# Pi_Zero_PITS.net
KiCad netlist of a schematic drawn in EAGLE
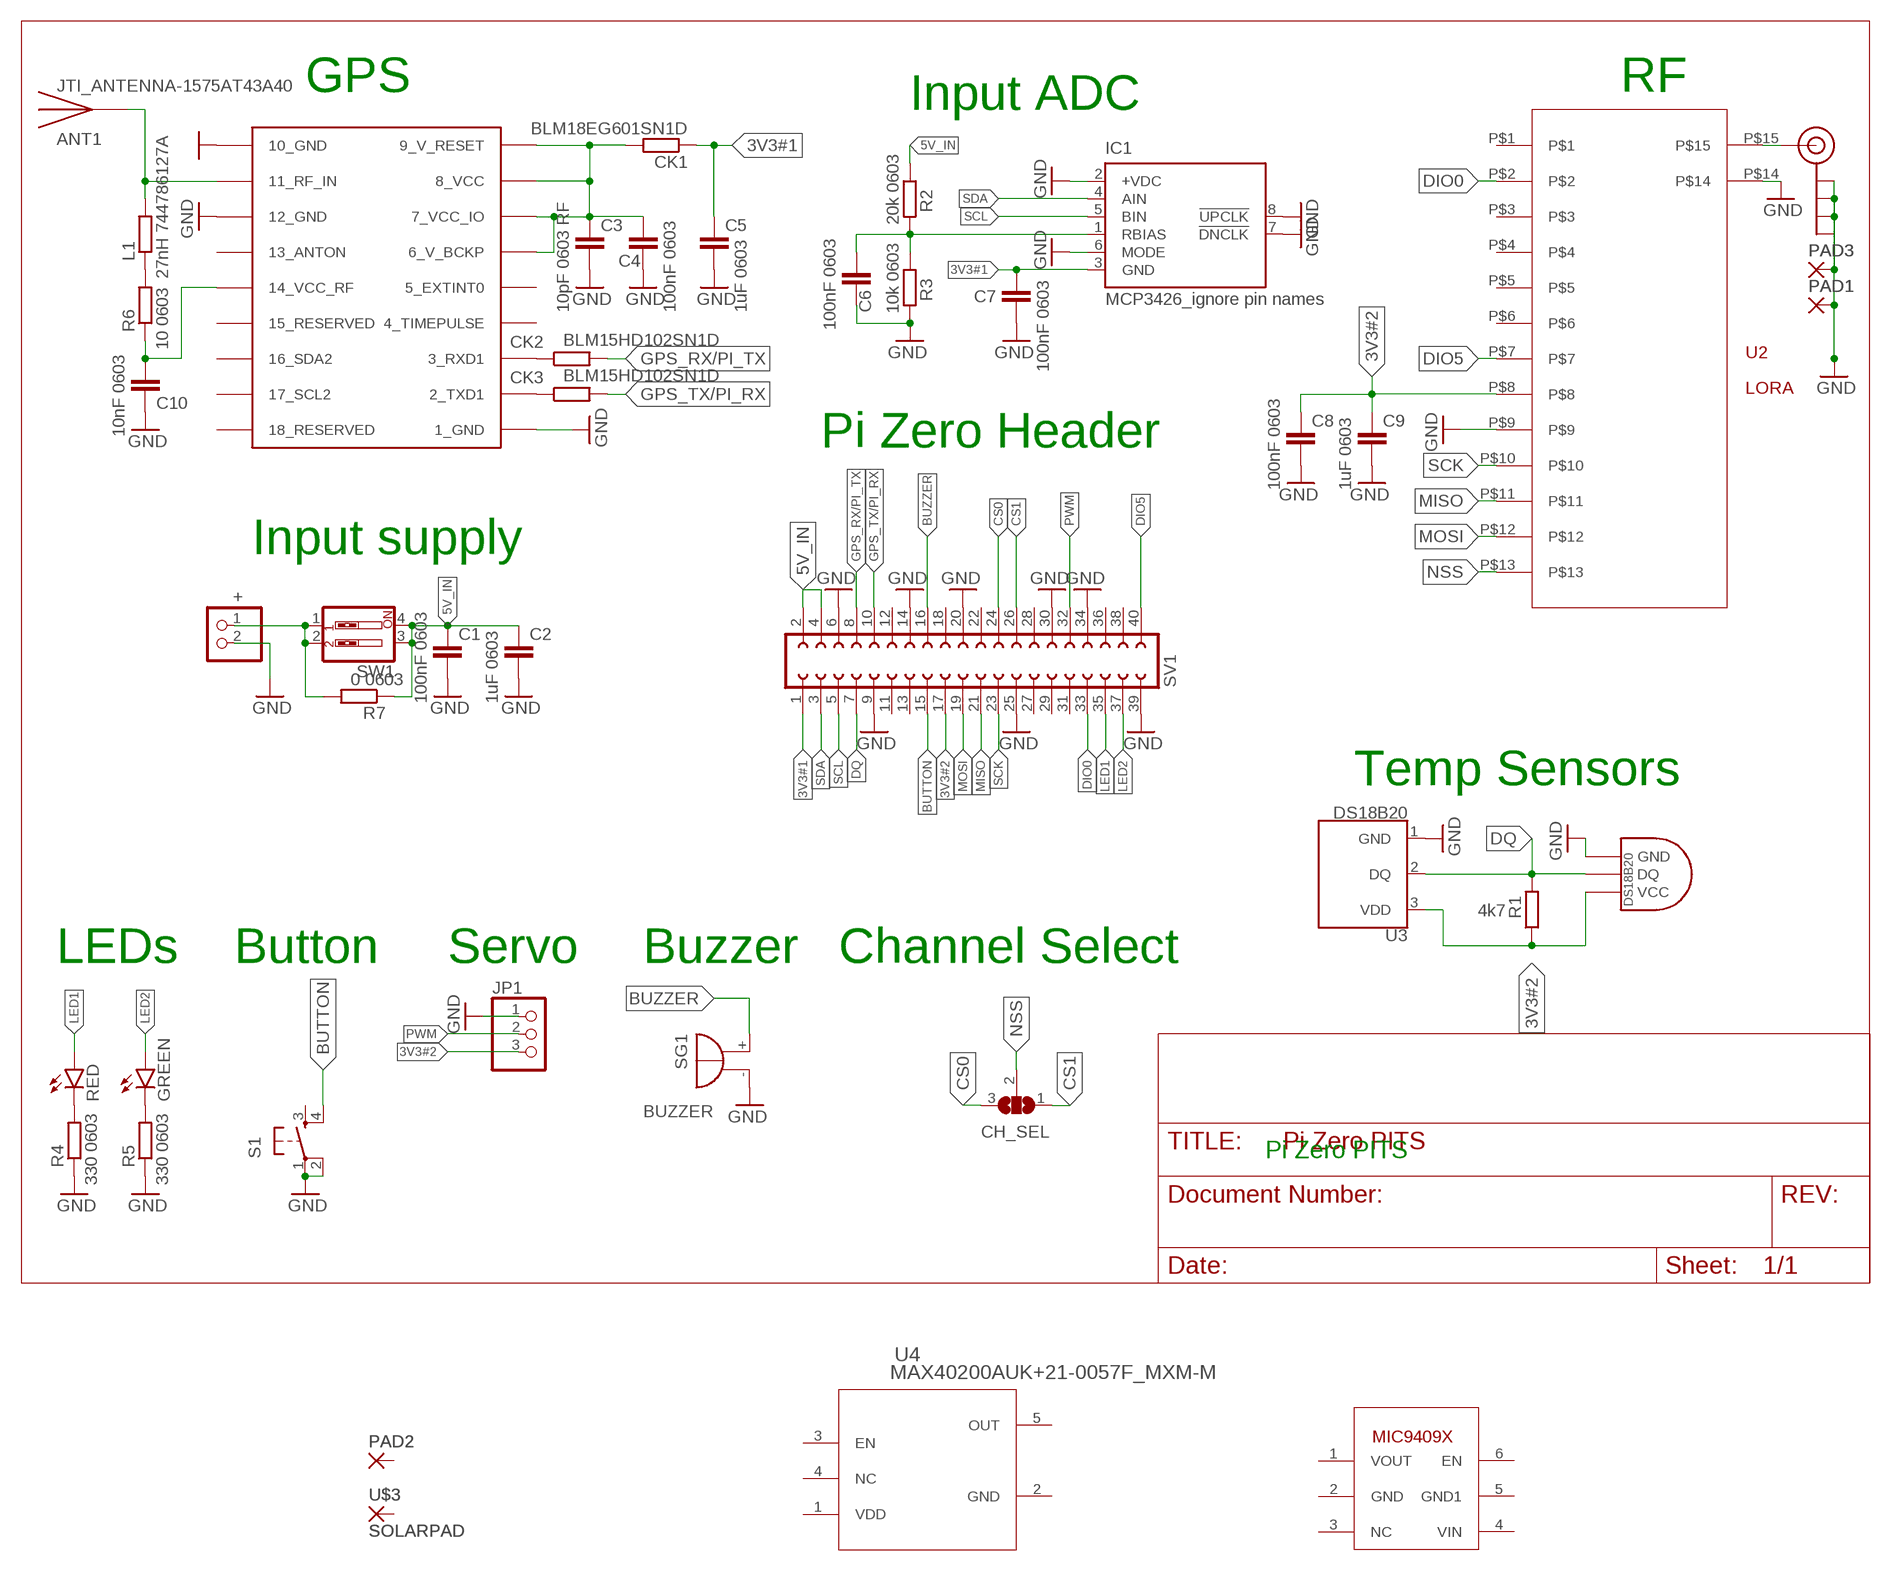
[diagram p0: schematic, sheet 1]

(export (version "E")
  (design (tool "Eeschema 10.0.6"))
  (components
    (comp (ref "+")
      (value "PINHD-1X2")
      (footprint "eagle-import:1X02")
      (libsource (lib "eagle-import") (part "PINHD-1X2"))
    )
    (comp (ref "ANT1")
      (value "JTI_ANTENNA-1575AT43A40")
      (footprint "eagle-import:JTI_ANTENNA-1575AT43A40")
      (libsource (lib "eagle-import") (part "JTI_ANTENNA-1575AT43A40"))
    )
    (comp (ref "C1")
      (value "100nF 0603")
      (footprint "eagle-import:C0603K")
      (libsource (lib "eagle-import") (part "C-EUC0603K"))
    )
    (comp (ref "C2")
      (value "1uF 0603")
      (footprint "eagle-import:C0603K")
      (libsource (lib "eagle-import") (part "C-EUC0603K"))
    )
    (comp (ref "C3")
      (value "10pF 0603 RF")
      (footprint "eagle-import:C0603K")
      (libsource (lib "eagle-import") (part "C-EUC0603K"))
    )
    (comp (ref "C4")
      (value "100nF 0603")
      (footprint "eagle-import:C0603K")
      (libsource (lib "eagle-import") (part "C-EUC0603K"))
    )
    (comp (ref "C5")
      (value "1uF 0603")
      (footprint "eagle-import:C0603K")
      (libsource (lib "eagle-import") (part "C-EUC0603K"))
    )
    (comp (ref "C6")
      (value "100nF 0603")
      (footprint "eagle-import:C0603K")
      (libsource (lib "eagle-import") (part "C-EUC0603K"))
    )
    (comp (ref "C7")
      (value "100nF 0603")
      (footprint "eagle-import:C0603K")
      (libsource (lib "eagle-import") (part "C-EUC0603K"))
    )
    (comp (ref "C8")
      (value "100nF 0603")
      (footprint "eagle-import:C0603K")
      (libsource (lib "eagle-import") (part "C-EUC0603K"))
    )
    (comp (ref "C9")
      (value "1uF 0603")
      (footprint "eagle-import:C0603K")
      (libsource (lib "eagle-import") (part "C-EUC0603K"))
    )
    (comp (ref "C10")
      (value "10nF 0603")
      (footprint "eagle-import:C0603K")
      (libsource (lib "eagle-import") (part "C-EUC0603K"))
    )
    (comp (ref "CH_SEL")
      (value "SJ2W")
      (footprint "eagle-import:SJ_2")
      (libsource (lib "eagle-import") (part "SJ2W"))
    )
    (comp (ref "CK1")
      (value "BLM18EG601SN1D")
      (footprint "eagle-import:R0603")
      (libsource (lib "eagle-import") (part "R-EU_R0603"))
    )
    (comp (ref "CK2")
      (value "BLM15HD102SN1D")
      (footprint "eagle-import:R0402")
      (libsource (lib "eagle-import") (part "R-EU_R0402"))
    )
    (comp (ref "CK3")
      (value "BLM15HD102SN1D")
      (footprint "eagle-import:R0402")
      (libsource (lib "eagle-import") (part "R-EU_R0402"))
    )
    (comp (ref "GREEN")
      (value "LEDSML0603")
      (footprint "eagle-import:SML0603")
      (libsource (lib "eagle-import") (part "LEDSML0603"))
    )
    (comp (ref "IC1")
      (value "MCP3426_ignore pin names")
      (footprint "eagle-import:SOIC08")
      (libsource (lib "eagle-import") (part "LS7183-SOIC"))
    )
    (comp (ref "J$2")
      (value "SMA_EDGE")
      (footprint "eagle-import:SMA-EDGE")
      (libsource (lib "eagle-import") (part "SMA_EDGE"))
    )
    (comp (ref "JP1")
      (value "PINHD-1X3")
      (footprint "eagle-import:1X03")
      (libsource (lib "eagle-import") (part "PINHD-1X3"))
    )
    (comp (ref "L1")
      (value "27nH 744786127A")
      (footprint "eagle-import:R0603")
      (libsource (lib "eagle-import") (part "R-EU_R0603"))
    )
    (comp (ref "PAD1")
      (value "SMD5")
      (footprint "eagle-import:SMD2,54-5,08")
      (libsource (lib "eagle-import") (part "SMD5"))
    )
    (comp (ref "PAD2")
      (value "SMD2SMD_KW")
      (footprint "eagle-import:SMD_SMALL")
      (libsource (lib "eagle-import") (part "SMD2SMD_KW"))
    )
    (comp (ref "PAD3")
      (value "SMD5")
      (footprint "eagle-import:SMD2,54-5,08")
      (libsource (lib "eagle-import") (part "SMD5"))
    )
    (comp (ref "R1")
      (value "4k7")
      (footprint "eagle-import:R0603")
      (libsource (lib "eagle-import") (part "R-EU_R0603"))
    )
    (comp (ref "R2")
      (value "20k 0603")
      (footprint "eagle-import:R0603")
      (libsource (lib "eagle-import") (part "R-EU_R0603"))
    )
    (comp (ref "R3")
      (value "10k 0603")
      (footprint "eagle-import:R0603")
      (libsource (lib "eagle-import") (part "R-EU_R0603"))
    )
    (comp (ref "R4")
      (value "330 0603")
      (footprint "eagle-import:R0603")
      (libsource (lib "eagle-import") (part "R-EU_R0603"))
    )
    (comp (ref "R5")
      (value "330 0603")
      (footprint "eagle-import:R0603")
      (libsource (lib "eagle-import") (part "R-EU_R0603"))
    )
    (comp (ref "R6")
      (value "10 0603")
      (footprint "eagle-import:R0603")
      (libsource (lib "eagle-import") (part "R-EU_R0603"))
    )
    (comp (ref "R7")
      (value "0 0603")
      (footprint "eagle-import:R0603")
      (libsource (lib "eagle-import") (part "R-EU_R0603"))
    )
    (comp (ref "RED")
      (value "LEDSML0603")
      (footprint "eagle-import:SML0603")
      (libsource (lib "eagle-import") (part "LEDSML0603"))
    )
    (comp (ref "S1")
      (value "DTS-6")
      (footprint "eagle-import:DTS-6")
      (libsource (lib "eagle-import") (part "DTS-6"))
    )
    (comp (ref "SG1")
      (value "BUZZER")
      (footprint "eagle-import:BMT1205XH7.5")
      (libsource (lib "eagle-import") (part "BMT1205XH7.5"))
    )
    (comp (ref "SV1")
      (value "FE20-2")
      (footprint "eagle-import:FE20-2")
      (libsource (lib "eagle-import") (part "FE20-2"))
    )
    (comp (ref "SW1")
      (value "SW_DIP-2")
      (footprint "eagle-import:EDG-02")
      (libsource (lib "eagle-import") (part "SW_DIP-2"))
    )
    (comp (ref "U$2")
      (value "MIC9409X_MIC9409X")
      (footprint "eagle-import:MIC9409X_DCK_R-PDSO-G6")
      (libsource (lib "eagle-import") (part "MIC9409X_MIC9409X"))
    )
    (comp (ref "U$3")
      (value "SOLARPAD")
      (footprint "eagle-import:SOLARMOUNT")
      (libsource (lib "eagle-import") (part "SOLARPAD"))
    )
    (comp (ref "U$4")
      (value "DS1820SOIC")
      (footprint "eagle-import:DS18B20_SOIC")
      (libsource (lib "eagle-import") (part "DS1820SOIC"))
    )
    (comp (ref "U1")
      (value "U1")
      (footprint "eagle-import:UBLOX_MAX-6")
      (libsource (lib "eagle-import") (part "UBLOX_MAX-6"))
    )
    (comp (ref "U2")
      (value "LORA")
      (footprint "eagle-import:LORA_DRF")
      (libsource (lib "eagle-import") (part "LORA"))
    )
    (comp (ref "U3")
      (value "DS18B20")
      (footprint "eagle-import:TO-92-AMMO")
      (libsource (lib "eagle-import") (part "DS18B20"))
    )
    (comp (ref "U4")
      (value "MAX40200AUK+21-0057F_MXM-M")
      (footprint "eagle-import:21-0057F_MXM-M")
      (fields
        (field (name "MANUFACTURER_PART_NUMBER") "MAX40200AUK+")
        (field (name "COPYRIGHT") "Copyright (C) 2018 Accelerated Designs. All rights reserved")
      )
      (libsource (lib "eagle-import") (part "MAX40200AUK+21-0057F_MXM-M"))
    )
  )
  (nets
    (net (code "1") (name "/VDD") (class "Default")
      (node (ref "U4") (pin "1") (pinfunction "VDD_1") (pintype "power_in"))
    )
    (net (code "2") (name "3V3#1") (class "Default")
      (node (ref "C5") (pin "1") (pinfunction "1_1") (pintype "passive"))
      (node (ref "C7") (pin "1") (pinfunction "1_1") (pintype "passive"))
      (node (ref "CK1") (pin "1") (pinfunction "1_1") (pintype "passive"))
      (node (ref "IC1") (pin "3") (pinfunction "GND_3") (pintype "power_in"))
      (node (ref "SV1") (pin "1") (pinfunction "1_1") (pintype "passive"))
    )
    (net (code "3") (name "3V3#2") (class "Default")
      (node (ref "C8") (pin "1") (pinfunction "1_1") (pintype "passive"))
      (node (ref "C9") (pin "1") (pinfunction "1_1") (pintype "passive"))
      (node (ref "JP1") (pin "3") (pinfunction "3_3") (pintype "passive"))
      (node (ref "R1") (pin "1") (pinfunction "1_1") (pintype "passive"))
      (node (ref "SV1") (pin "17") (pinfunction "17_17") (pintype "passive"))
      (node (ref "U$4") (pin "VCC") (pinfunction "VCC_VCC") (pintype "power_in"))
      (node (ref "U2") (pin "P$8") (pinfunction "P$8_P$8") (pintype "bidirectional"))
      (node (ref "U3") (pin "3") (pinfunction "VDD_3") (pintype "power_in"))
    )
    (net (code "4") (name "5V_IN") (class "Default")
      (node (ref "C1") (pin "1") (pinfunction "1_1") (pintype "passive"))
      (node (ref "C2") (pin "1") (pinfunction "1_1") (pintype "passive"))
      (node (ref "R2") (pin "1") (pinfunction "1_1") (pintype "passive"))
      (node (ref "R7") (pin "1") (pinfunction "1_1") (pintype "passive"))
      (node (ref "SV1") (pin "2") (pinfunction "2_2") (pintype "passive"))
      (node (ref "SV1") (pin "4") (pinfunction "4_4") (pintype "passive"))
      (node (ref "SW1") (pin "3") (pinfunction "3_3") (pintype "passive"))
      (node (ref "SW1") (pin "4") (pinfunction "4_4") (pintype "passive"))
    )
    (net (code "5") (name "BUTTON") (class "Default")
      (node (ref "S1") (pin "4") (pinfunction "4_4") (pintype "passive"))
      (node (ref "SV1") (pin "15") (pinfunction "15_15") (pintype "passive"))
    )
    (net (code "6") (name "BUZZER") (class "Default")
      (node (ref "SG1") (pin "+") (pinfunction "+_+") (pintype "passive"))
      (node (ref "SV1") (pin "16") (pinfunction "16_16") (pintype "passive"))
    )
    (net (code "7") (name "CS0") (class "Default")
      (node (ref "CH_SEL") (pin "3") (pinfunction "3_3") (pintype "passive"))
      (node (ref "SV1") (pin "24") (pinfunction "24_24") (pintype "passive"))
    )
    (net (code "8") (name "CS1") (class "Default")
      (node (ref "CH_SEL") (pin "1") (pinfunction "1_1") (pintype "passive"))
      (node (ref "SV1") (pin "26") (pinfunction "26_26") (pintype "passive"))
    )
    (net (code "9") (name "DIO0") (class "Default")
      (node (ref "SV1") (pin "33") (pinfunction "33_33") (pintype "passive"))
      (node (ref "U2") (pin "P$2") (pinfunction "P$2_P$2") (pintype "bidirectional"))
    )
    (net (code "10") (name "DIO5") (class "Default")
      (node (ref "SV1") (pin "40") (pinfunction "40_40") (pintype "passive"))
      (node (ref "U2") (pin "P$7") (pinfunction "P$7_P$7") (pintype "bidirectional"))
    )
    (net (code "11") (name "DQ") (class "Default")
      (node (ref "R1") (pin "2") (pinfunction "2_2") (pintype "passive"))
      (node (ref "SV1") (pin "7") (pinfunction "7_7") (pintype "passive"))
      (node (ref "U$4") (pin "DQ") (pinfunction "DQ_DQ") (pintype "bidirectional"))
      (node (ref "U3") (pin "2") (pinfunction "DQ_2") (pintype "bidirectional"))
    )
    (net (code "12") (name "GND") (class "Default")
      (node (ref "+") (pin "2") (pinfunction "2_2") (pintype "passive"))
      (node (ref "C1") (pin "2") (pinfunction "2_2") (pintype "passive"))
      (node (ref "C10") (pin "2") (pinfunction "2_2") (pintype "passive"))
      (node (ref "C2") (pin "2") (pinfunction "2_2") (pintype "passive"))
      (node (ref "C3") (pin "2") (pinfunction "2_2") (pintype "passive"))
      (node (ref "C4") (pin "2") (pinfunction "2_2") (pintype "passive"))
      (node (ref "C5") (pin "2") (pinfunction "2_2") (pintype "passive"))
      (node (ref "C6") (pin "2") (pinfunction "2_2") (pintype "passive"))
      (node (ref "C7") (pin "2") (pinfunction "2_2") (pintype "passive"))
      (node (ref "C8") (pin "2") (pinfunction "2_2") (pintype "passive"))
      (node (ref "C9") (pin "2") (pinfunction "2_2") (pintype "passive"))
      (node (ref "IC1") (pin "2") (pinfunction "+VDC_2") (pintype "input"))
      (node (ref "IC1") (pin "6") (pinfunction "MODE_6") (pintype "input"))
      (node (ref "IC1") (pin "7") (pinfunction "~{DNCLK}_7") (pintype "input"))
      (node (ref "IC1") (pin "8") (pinfunction "~{UPCLK}_8") (pintype "input"))
      (node (ref "J$2") (pin "GND@0") (pinfunction "GND_GND@0") (pintype "bidirectional"))
      (node (ref "J$2") (pin "GND@1") (pinfunction "GND_GND@1") (pintype "bidirectional"))
      (node (ref "J$2") (pin "GND@2") (pinfunction "GND_GND@2") (pintype "bidirectional"))
      (node (ref "J$2") (pin "GND@3") (pinfunction "GND_GND@3") (pintype "bidirectional"))
      (node (ref "JP1") (pin "1") (pinfunction "1_1") (pintype "passive"))
      (node (ref "PAD1") (pin "1") (pinfunction "P_1") (pintype "passive"))
      (node (ref "PAD3") (pin "1") (pinfunction "P_1") (pintype "passive"))
      (node (ref "R3") (pin "2") (pinfunction "2_2") (pintype "passive"))
      (node (ref "R4") (pin "1") (pinfunction "1_1") (pintype "passive"))
      (node (ref "R5") (pin "1") (pinfunction "1_1") (pintype "passive"))
      (node (ref "S1") (pin "1") (pinfunction "1_1") (pintype "passive"))
      (node (ref "S1") (pin "2") (pinfunction "2_2") (pintype "passive"))
      (node (ref "SG1") (pin "-") (pinfunction "-_-") (pintype "passive"))
      (node (ref "SV1") (pin "14") (pinfunction "14_14") (pintype "passive"))
      (node (ref "SV1") (pin "20") (pinfunction "20_20") (pintype "passive"))
      (node (ref "SV1") (pin "25") (pinfunction "25_25") (pintype "passive"))
      (node (ref "SV1") (pin "30") (pinfunction "30_30") (pintype "passive"))
      (node (ref "SV1") (pin "34") (pinfunction "34_34") (pintype "passive"))
      (node (ref "SV1") (pin "39") (pinfunction "39_39") (pintype "passive"))
      (node (ref "SV1") (pin "6") (pinfunction "6_6") (pintype "passive"))
      (node (ref "SV1") (pin "9") (pinfunction "9_9") (pintype "passive"))
      (node (ref "U$4") (pin "GND") (pinfunction "GND_GND") (pintype "power_in"))
      (node (ref "U1") (pin "10_GND") (pinfunction "10_GND_10_GND") (pintype "power_in"))
      (node (ref "U1") (pin "12_GND") (pinfunction "12_GND_12_GND") (pintype "power_in"))
      (node (ref "U1") (pin "1_GND") (pinfunction "1_GND_1_GND") (pintype "power_in"))
      (node (ref "U2") (pin "P$14") (pinfunction "P$14_P$14") (pintype "bidirectional"))
      (node (ref "U2") (pin "P$9") (pinfunction "P$9_P$9") (pintype "bidirectional"))
      (node (ref "U3") (pin "1") (pinfunction "GND_1") (pintype "power_in"))
    )
    (net (code "13") (name "GPS_RX{slash}PI_TX") (class "Default")
      (node (ref "CK2") (pin "2") (pinfunction "2_2") (pintype "passive"))
      (node (ref "SV1") (pin "8") (pinfunction "8_8") (pintype "passive"))
    )
    (net (code "14") (name "GPS_TX{slash}PI_RX") (class "Default")
      (node (ref "CK3") (pin "2") (pinfunction "2_2") (pintype "passive"))
      (node (ref "SV1") (pin "10") (pinfunction "10_10") (pintype "passive"))
    )
    (net (code "15") (name "LED1") (class "Default")
      (node (ref "RED") (pin "A") (pinfunction "A_A") (pintype "passive"))
      (node (ref "SV1") (pin "35") (pinfunction "35_35") (pintype "passive"))
    )
    (net (code "16") (name "LED2") (class "Default")
      (node (ref "GREEN") (pin "A") (pinfunction "A_A") (pintype "passive"))
      (node (ref "SV1") (pin "37") (pinfunction "37_37") (pintype "passive"))
    )
    (net (code "17") (name "MISO") (class "Default")
      (node (ref "SV1") (pin "21") (pinfunction "21_21") (pintype "passive"))
      (node (ref "U2") (pin "P$11") (pinfunction "P$11_P$11") (pintype "bidirectional"))
    )
    (net (code "18") (name "MOSI") (class "Default")
      (node (ref "SV1") (pin "19") (pinfunction "19_19") (pintype "passive"))
      (node (ref "U2") (pin "P$12") (pinfunction "P$12_P$12") (pintype "bidirectional"))
    )
    (net (code "19") (name "NSS") (class "Default")
      (node (ref "CH_SEL") (pin "2") (pinfunction "2_2") (pintype "passive"))
      (node (ref "U2") (pin "P$13") (pinfunction "P$13_P$13") (pintype "bidirectional"))
    )
    (net (code "20") (name "Net-(+-Pad1)") (class "Default")
      (node (ref "+") (pin "1") (pinfunction "1_1") (pintype "passive"))
      (node (ref "R7") (pin "2") (pinfunction "2_2") (pintype "passive"))
      (node (ref "SW1") (pin "1") (pinfunction "1_1") (pintype "passive"))
      (node (ref "SW1") (pin "2") (pinfunction "2_2") (pintype "passive"))
    )
    (net (code "21") (name "Net-(ANT1-PadFEED)") (class "Default")
      (node (ref "ANT1") (pin "FEED") (pinfunction "FEED_FEED") (pintype "bidirectional"))
      (node (ref "L1") (pin "2") (pinfunction "2_2") (pintype "passive"))
      (node (ref "U1") (pin "11_RF_IN") (pinfunction "11_RF_IN_11_RF_IN") (pintype "bidirectional"))
    )
    (net (code "22") (name "Net-(C3-Pad1)") (class "Default")
      (node (ref "C3") (pin "1") (pinfunction "1_1") (pintype "passive"))
      (node (ref "C4") (pin "1") (pinfunction "1_1") (pintype "passive"))
      (node (ref "CK1") (pin "2") (pinfunction "2_2") (pintype "passive"))
      (node (ref "U1") (pin "6_V_BCKP") (pinfunction "6_V_BCKP_6_V_BCKP") (pintype "bidirectional"))
      (node (ref "U1") (pin "7_VCC_IO") (pinfunction "7_VCC_IO_7_VCC_IO") (pintype "power_in"))
      (node (ref "U1") (pin "8_VCC") (pinfunction "8_VCC_8_VCC") (pintype "power_in"))
      (node (ref "U1") (pin "9_V_RESET") (pinfunction "9_V_RESET_9_V_RESET") (pintype "power_in"))
    )
    (net (code "23") (name "Net-(C10-Pad1)") (class "Default")
      (node (ref "C10") (pin "1") (pinfunction "1_1") (pintype "passive"))
      (node (ref "R6") (pin "1") (pinfunction "1_1") (pintype "passive"))
      (node (ref "U1") (pin "14_VCC_RF") (pinfunction "14_VCC_RF_14_VCC_RF") (pintype "bidirectional"))
    )
    (net (code "24") (name "Net-(CK2-Pad1)") (class "Default")
      (node (ref "CK2") (pin "1") (pinfunction "1_1") (pintype "passive"))
      (node (ref "U1") (pin "3_RXD1") (pinfunction "3_RXD1_3_RXD1") (pintype "bidirectional"))
    )
    (net (code "25") (name "Net-(CK3-Pad1)") (class "Default")
      (node (ref "CK3") (pin "1") (pinfunction "1_1") (pintype "passive"))
      (node (ref "U1") (pin "2_TXD1") (pinfunction "2_TXD1_2_TXD1") (pintype "bidirectional"))
    )
    (net (code "26") (name "Net-(GREEN-PadC)") (class "Default")
      (node (ref "GREEN") (pin "C") (pinfunction "C_C") (pintype "passive"))
      (node (ref "R5") (pin "2") (pinfunction "2_2") (pintype "passive"))
    )
    (net (code "27") (name "Net-(IC1-RBIAS)") (class "Default")
      (node (ref "C6") (pin "1") (pinfunction "1_1") (pintype "passive"))
      (node (ref "IC1") (pin "1") (pinfunction "RBIAS_1") (pintype "input"))
      (node (ref "R2") (pin "2") (pinfunction "2_2") (pintype "passive"))
      (node (ref "R3") (pin "1") (pinfunction "1_1") (pintype "passive"))
    )
    (net (code "28") (name "Net-(J$2-SIGNAL)") (class "Default")
      (node (ref "J$2") (pin "SIG") (pinfunction "SIGNAL_SIG") (pintype "bidirectional"))
      (node (ref "U2") (pin "P$15") (pinfunction "P$15_P$15") (pintype "bidirectional"))
    )
    (net (code "29") (name "Net-(L1-Pad1)") (class "Default")
      (node (ref "L1") (pin "1") (pinfunction "1_1") (pintype "passive"))
      (node (ref "R6") (pin "2") (pinfunction "2_2") (pintype "passive"))
    )
    (net (code "30") (name "Net-(R4-Pad2)") (class "Default")
      (node (ref "R4") (pin "2") (pinfunction "2_2") (pintype "passive"))
      (node (ref "RED") (pin "C") (pinfunction "C_C") (pintype "passive"))
    )
    (net (code "31") (name "PWM") (class "Default")
      (node (ref "JP1") (pin "2") (pinfunction "2_2") (pintype "passive"))
      (node (ref "SV1") (pin "32") (pinfunction "32_32") (pintype "passive"))
    )
    (net (code "32") (name "SCK") (class "Default")
      (node (ref "SV1") (pin "23") (pinfunction "23_23") (pintype "passive"))
      (node (ref "U2") (pin "P$10") (pinfunction "P$10_P$10") (pintype "bidirectional"))
    )
    (net (code "33") (name "SCL") (class "Default")
      (node (ref "IC1") (pin "5") (pinfunction "BIN_5") (pintype "input"))
      (node (ref "SV1") (pin "5") (pinfunction "5_5") (pintype "passive"))
    )
    (net (code "34") (name "SDA") (class "Default")
      (node (ref "IC1") (pin "4") (pinfunction "AIN_4") (pintype "input"))
      (node (ref "SV1") (pin "3") (pinfunction "3_3") (pintype "passive"))
    )
    (net (code "35") (name "unconnected-(PAD2-P-Pad1)") (class "Default")
      (node (ref "PAD2") (pin "1") (pinfunction "P_1") (pintype "passive"))
    )
    (net (code "36") (name "unconnected-(S1-Pad3)") (class "Default")
      (node (ref "S1") (pin "3") (pinfunction "3_3") (pintype "passive"))
    )
    (net (code "37") (name "unconnected-(SV1-Pad11)") (class "Default")
      (node (ref "SV1") (pin "11") (pinfunction "11_11") (pintype "passive"))
    )
    (net (code "38") (name "unconnected-(SV1-Pad12)") (class "Default")
      (node (ref "SV1") (pin "12") (pinfunction "12_12") (pintype "passive"))
    )
    (net (code "39") (name "unconnected-(SV1-Pad13)") (class "Default")
      (node (ref "SV1") (pin "13") (pinfunction "13_13") (pintype "passive"))
    )
    (net (code "40") (name "unconnected-(SV1-Pad18)") (class "Default")
      (node (ref "SV1") (pin "18") (pinfunction "18_18") (pintype "passive"))
    )
    (net (code "41") (name "unconnected-(SV1-Pad22)") (class "Default")
      (node (ref "SV1") (pin "22") (pinfunction "22_22") (pintype "passive"))
    )
    (net (code "42") (name "unconnected-(SV1-Pad27)") (class "Default")
      (node (ref "SV1") (pin "27") (pinfunction "27_27") (pintype "passive"))
    )
    (net (code "43") (name "unconnected-(SV1-Pad28)") (class "Default")
      (node (ref "SV1") (pin "28") (pinfunction "28_28") (pintype "passive"))
    )
    (net (code "44") (name "unconnected-(SV1-Pad29)") (class "Default")
      (node (ref "SV1") (pin "29") (pinfunction "29_29") (pintype "passive"))
    )
    (net (code "45") (name "unconnected-(SV1-Pad31)") (class "Default")
      (node (ref "SV1") (pin "31") (pinfunction "31_31") (pintype "passive"))
    )
    (net (code "46") (name "unconnected-(SV1-Pad36)") (class "Default")
      (node (ref "SV1") (pin "36") (pinfunction "36_36") (pintype "passive"))
    )
    (net (code "47") (name "unconnected-(SV1-Pad38)") (class "Default")
      (node (ref "SV1") (pin "38") (pinfunction "38_38") (pintype "passive"))
    )
    (net (code "48") (name "unconnected-(U$2-EN-Pad6)") (class "Default")
      (node (ref "U$2") (pin "6") (pinfunction "EN_6") (pintype "bidirectional"))
    )
    (net (code "49") (name "unconnected-(U$2-GND-Pad2)") (class "Default")
      (node (ref "U$2") (pin "2") (pinfunction "GND_2") (pintype "bidirectional"))
    )
    (net (code "50") (name "unconnected-(U$2-GND1-Pad5)") (class "Default")
      (node (ref "U$2") (pin "5") (pinfunction "GND1_5") (pintype "bidirectional"))
    )
    (net (code "51") (name "unconnected-(U$2-NC-Pad3)") (class "Default")
      (node (ref "U$2") (pin "3") (pinfunction "NC_3") (pintype "bidirectional"))
    )
    (net (code "52") (name "unconnected-(U$2-VIN-Pad4)") (class "Default")
      (node (ref "U$2") (pin "4") (pinfunction "VIN_4") (pintype "bidirectional"))
    )
    (net (code "53") (name "unconnected-(U$2-VOUT-Pad1)") (class "Default")
      (node (ref "U$2") (pin "1") (pinfunction "VOUT_1") (pintype "bidirectional"))
    )
    (net (code "54") (name "unconnected-(U$3-P-Pad1)") (class "Default")
      (node (ref "U$3") (pin "1") (pinfunction "P_1") (pintype "passive"))
    )
    (net (code "55") (name "unconnected-(U1-Pad4_TIMEPULSE)") (class "Default")
      (node (ref "U1") (pin "4_TIMEPULSE") (pinfunction "4_TIMEPULSE_4_TIMEPULSE") (pintype "bidirectional"))
    )
    (net (code "56") (name "unconnected-(U1-Pad5_EXTINT0)") (class "Default")
      (node (ref "U1") (pin "5_EXTINT0") (pinfunction "5_EXTINT0_5_EXTINT0") (pintype "bidirectional"))
    )
    (net (code "57") (name "unconnected-(U1-Pad13_ANTON)") (class "Default")
      (node (ref "U1") (pin "13_ANTON") (pinfunction "13_ANTON_13_ANTON") (pintype "bidirectional"))
    )
    (net (code "58") (name "unconnected-(U1-Pad15_RESERVED)") (class "Default")
      (node (ref "U1") (pin "15_RESERVED") (pinfunction "15_RESERVED_15_RESERVED") (pintype "bidirectional"))
    )
    (net (code "59") (name "unconnected-(U1-Pad16_SDA2)") (class "Default")
      (node (ref "U1") (pin "16_SDA2") (pinfunction "16_SDA2_16_SDA2") (pintype "bidirectional"))
    )
    (net (code "60") (name "unconnected-(U1-Pad17_SCL2)") (class "Default")
      (node (ref "U1") (pin "17_SCL2") (pinfunction "17_SCL2_17_SCL2") (pintype "bidirectional"))
    )
    (net (code "61") (name "unconnected-(U1-Pad18_RESERVED)") (class "Default")
      (node (ref "U1") (pin "18_RESERVED") (pinfunction "18_RESERVED_18_RESERVED") (pintype "bidirectional"))
    )
    (net (code "62") (name "unconnected-(U2-PadP$1)") (class "Default")
      (node (ref "U2") (pin "P$1") (pinfunction "P$1_P$1") (pintype "bidirectional"))
    )
    (net (code "63") (name "unconnected-(U2-PadP$3)") (class "Default")
      (node (ref "U2") (pin "P$3") (pinfunction "P$3_P$3") (pintype "bidirectional"))
    )
    (net (code "64") (name "unconnected-(U2-PadP$4)") (class "Default")
      (node (ref "U2") (pin "P$4") (pinfunction "P$4_P$4") (pintype "bidirectional"))
    )
    (net (code "65") (name "unconnected-(U2-PadP$5)") (class "Default")
      (node (ref "U2") (pin "P$5") (pinfunction "P$5_P$5") (pintype "bidirectional"))
    )
    (net (code "66") (name "unconnected-(U2-PadP$6)") (class "Default")
      (node (ref "U2") (pin "P$6") (pinfunction "P$6_P$6") (pintype "bidirectional"))
    )
    (net (code "67") (name "unconnected-(U4-EN-Pad3)") (class "Default")
      (node (ref "U4") (pin "3") (pinfunction "EN_3") (pintype "passive"))
    )
    (net (code "68") (name "unconnected-(U4-GND-Pad2)") (class "Default")
      (node (ref "U4") (pin "2") (pinfunction "GND_2") (pintype "passive"))
    )
    (net (code "69") (name "unconnected-(U4-NC-Pad4)") (class "Default")
      (node (ref "U4") (pin "4") (pinfunction "NC_4") (pintype "no_connect"))
    )
    (net (code "70") (name "unconnected-(U4-OUT-Pad5)") (class "Default")
      (node (ref "U4") (pin "5") (pinfunction "OUT_5") (pintype "output"))
    )
  )
)
